# power_supply.net
KiCad netlist of a schematic drawn in Altium Designer
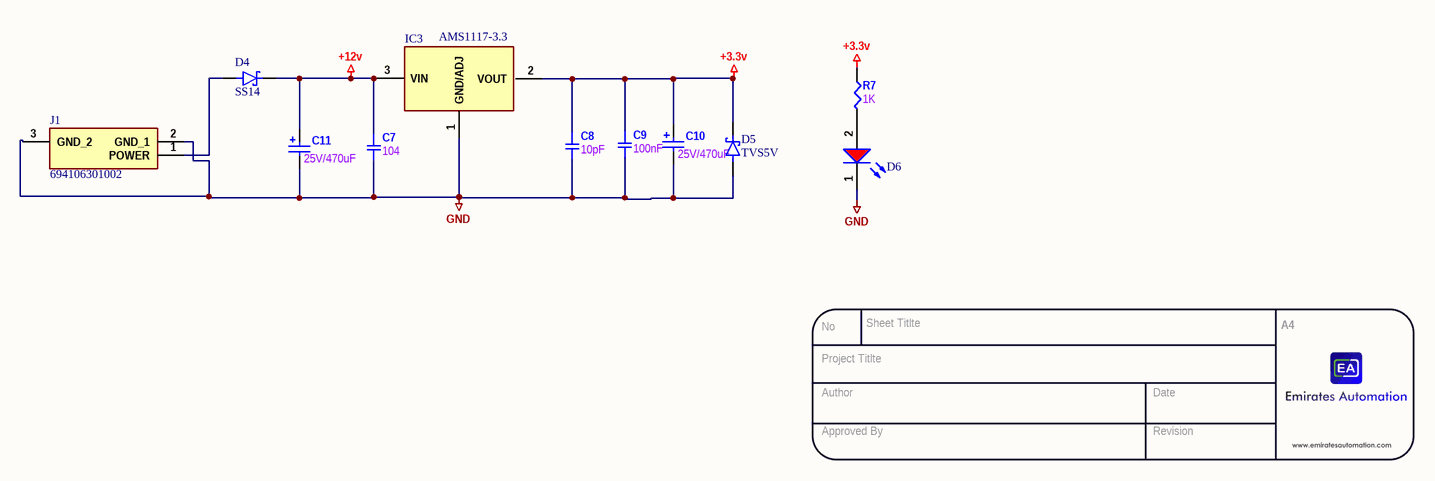
[diagram p0: power supply.SchDoc]

(export (version "E")
  (design (tool "Eeschema 10.0.6"))
  (components
    (comp (ref "C7")
      (value "104")
      (footprint "SMD-1206C")
      (description "CAP CER 0.033UF 250V X7T 1206")
      (fields
        (field (name "DIGI-KEY PART NUMBER") "490-13989-1-ND")
        (field (name "PART NUMBER") "GC331AD72E333KX01D")
      )
      (libsource (lib "capacitor_murata_1206") (part "GC331AD72E333KX01D"))
    )
    (comp (ref "C8")
      (value "10pF")
      (footprint "SMD-1206C")
      (description "CAP CER 10PF 50V NP0 1206")
      (fields
        (field (name "DIGI-KEY PART NUMBER") "490-13989-1-ND")
        (field (name "PART NUMBER") "GC331AD72E333KX01D")
      )
      (libsource (lib "capacitor_murata_1206") (part "GC331AD72E333KX01D"))
    )
    (comp (ref "C9")
      (value "100nF")
      (footprint "SMD-1206C")
      (description "CAP CER 0.1UF 50V X7R 1206")
      (fields
        (field (name "DIGI-KEY PART NUMBER") "490-13989-1-ND")
        (field (name "PART NUMBER") "GC331AD72E333KX01D")
      )
      (libsource (lib "capacitor_murata_1206") (part "GC331AD72E333KX01D"))
    )
    (comp (ref "C10")
      (value "25V/470uF")
      (footprint "WCAP-ATUL_8x11.5x3.5")
      (description "WCAP-ATUL Aluminum Electrolytic Capacitors, 8x11.5mm, 25 Vdc, 220 uF")
      (fields (field (name "PART NUMBER") "860040474004") (field (name "PUBLISHER") "Wurth Elektronik"))
      (libsource (lib "5mm to 18mm Through hole capactor ALTIUM-WCAP-ATUL-rev17a") (part "860040474004"))
    )
    (comp (ref "C11")
      (value "25V/470uF")
      (footprint "WCAP-ATUL_8x11.5x3.5")
      (description "WCAP-ATUL Aluminum Electrolytic Capacitors, 8x11.5mm, 25 Vdc, 220 uF")
      (fields (field (name "PART NUMBER") "860040474004") (field (name "PUBLISHER") "Wurth Elektronik"))
      (libsource (lib "5mm to 18mm Through hole capactor ALTIUM-WCAP-ATUL-rev17a") (part "860040474004"))
    )
    (comp (ref "D4") (value "SS14") (footprint "DIOM4325X250N") (libsource (lib "SS14") (part "SS14")))
    (comp (ref "D5")
      (value "TVS5V")
      (footprint "DIOM4325X250N")
      (fields (field (name "MP") "SS14"))
      (libsource (lib "SS14") (part "SS14"))
    )
    (comp (ref "D6")
      (value "Red, 2V, 140°")
      (footprint "WL-SMCD_0603")
      (description "WL-SMCD Mono-color Chip LED Diffused, SMT, size 0603, Red, 2V, 140°")
      (fields
        (field (name "MANUFACTURER PART NUMBER") "150060RS55040")
        (field (name "MANUFACTURER") "Wurth Elektronik")
      )
      (libsource (lib "wurth led 0603") (part "150060RS55040"))
    )
    (comp (ref "IC3")
      (value "AMS1117-3.3")
      (footprint "SamacSys:SOT229P700X180-4N")
      (description "Integrated Circuit")
      (libsource (lib "SamacSys") (part "AMS1117-3.3"))
    )
    (comp (ref "J1")
      (value "694106301002")
      (footprint "SamacSys:694106301002_1")
      (description "Connector")
      (fields (field (name "MOUSER PART NUMBER") "710-694106301002"))
      (libsource (lib "*") (part "694106301002"))
    )
    (comp (ref "R7")
      (value "1K")
      (footprint "SMD-0805-RES")
      (description "RES SMD 1 OHM 1% 1/3W 0805")
      (fields (field (name "PART NUMBER") "ERJ-6BQF1R0V") (field (name "DIGI-KEY PART NUMBER") "P17499CT-ND"))
      (libsource (lib "Panasonic_ERJ_0805") (part "ERJ-6BQF1R0V"))
    )
  )
  (nets
    (net (code "1") (name "+3.3v") (class "Default")
      (node (ref "C10") (pin "1") (pinfunction "P_1") (pintype "passive"))
      (node (ref "C8") (pin "1") (pinfunction "1_1") (pintype "passive"))
      (node (ref "C9") (pin "1") (pinfunction "1_1") (pintype "passive"))
      (node (ref "D5") (pin "C") (pinfunction "K_C") (pintype "passive"))
      (node (ref "IC3") (pin "2") (pinfunction "VOUT_2") (pintype "passive"))
      (node (ref "R7") (pin "1") (pinfunction "1_1") (pintype "passive"))
    )
    (net (code "2") (name "+12v") (class "Default")
      (node (ref "C11") (pin "1") (pinfunction "P_1") (pintype "passive"))
      (node (ref "C7") (pin "1") (pinfunction "1_1") (pintype "passive"))
      (node (ref "D4") (pin "C") (pinfunction "K_C") (pintype "passive"))
      (node (ref "IC3") (pin "3") (pinfunction "VIN_3") (pintype "passive"))
    )
    (net (code "3") (name "GND") (class "Default")
      (node (ref "C10") (pin "2") (pinfunction "N_2") (pintype "passive"))
      (node (ref "C11") (pin "2") (pinfunction "N_2") (pintype "passive"))
      (node (ref "C7") (pin "2") (pinfunction "2_2") (pintype "passive"))
      (node (ref "C8") (pin "2") (pinfunction "2_2") (pintype "passive"))
      (node (ref "C9") (pin "2") (pinfunction "2_2") (pintype "passive"))
      (node (ref "D5") (pin "A") (pinfunction "A_A") (pintype "passive"))
      (node (ref "D6") (pin "1") (pinfunction "K_1") (pintype "passive"))
      (node (ref "IC3") (pin "1") (pinfunction "GND/ADJ_1") (pintype "passive"))
      (node (ref "J1") (pin "2") (pinfunction "GND_1_2") (pintype "passive"))
      (node (ref "J1") (pin "3") (pinfunction "GND_2_3") (pintype "passive"))
    )
    (net (code "4") (name "Net-(D6-A)") (class "Default")
      (node (ref "D6") (pin "2") (pinfunction "A_2") (pintype "passive"))
      (node (ref "R7") (pin "2") (pinfunction "2_2") (pintype "passive"))
    )
    (net (code "5") (name "Net-(J1-POWER)") (class "Default")
      (node (ref "D4") (pin "A") (pinfunction "A_A") (pintype "passive"))
      (node (ref "J1") (pin "1") (pinfunction "POWER_1") (pintype "passive"))
    )
  )
)
